# ADC.net
KiCad netlist of a schematic drawn in Altium Designer
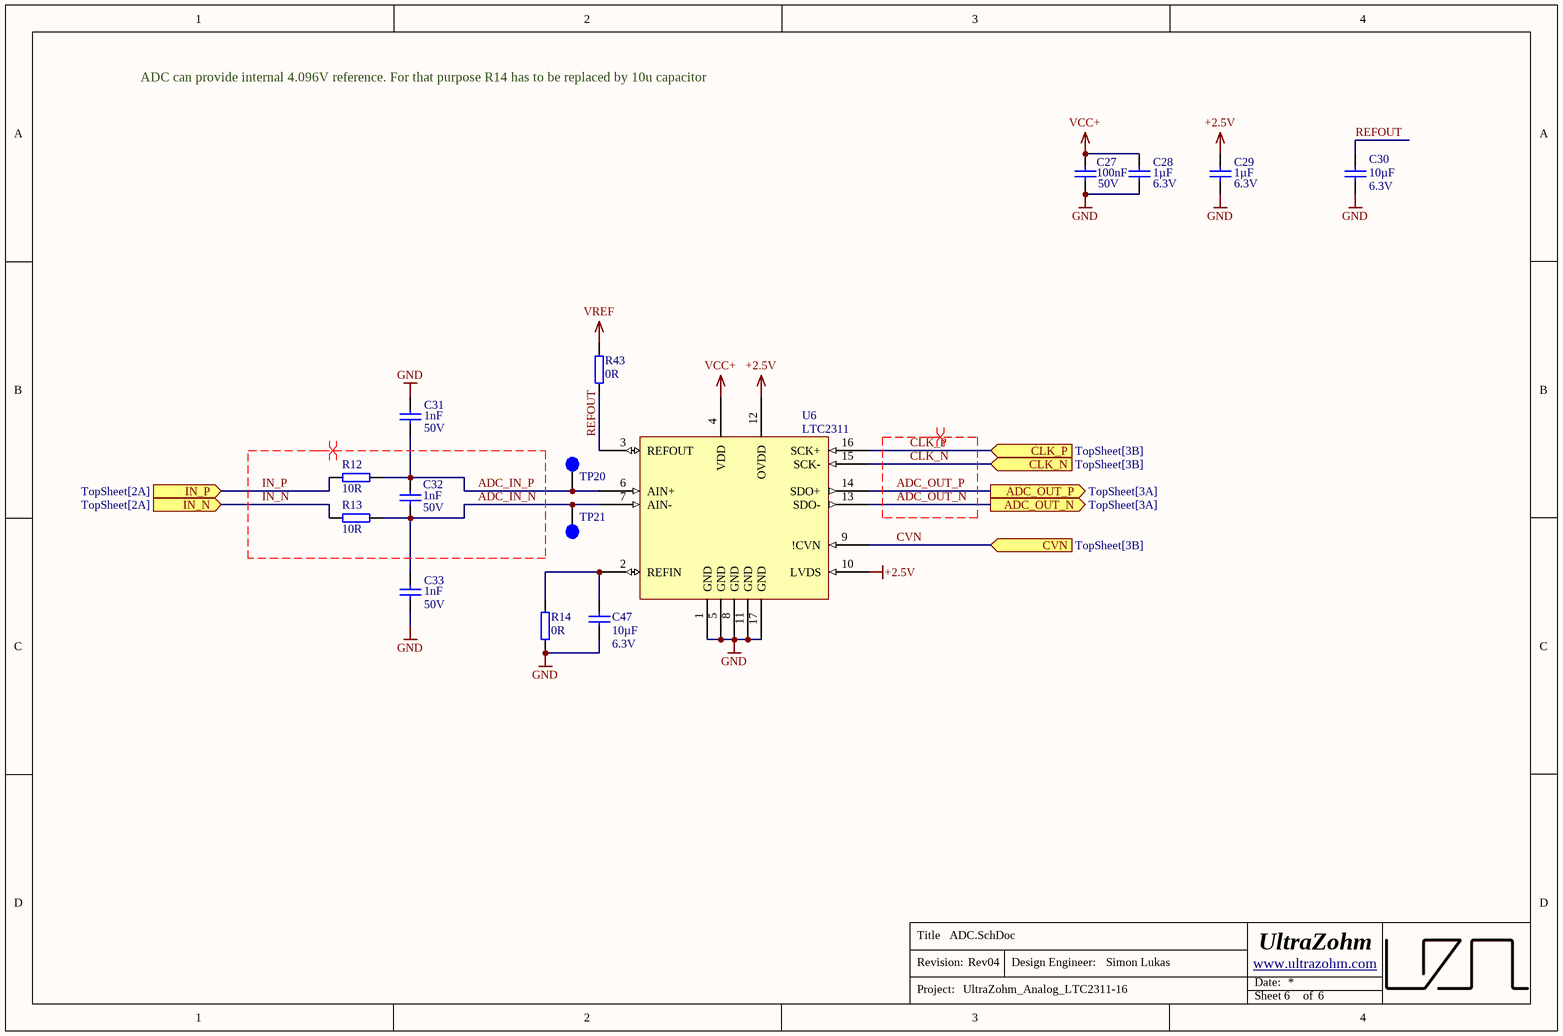
[diagram p0: ADC.SchDoc]

(export (version "E")
  (design (tool "Eeschema 10.0.6"))
  (components
    (comp (ref "C27")
      (value "100nF")
      (footprint "CAPC1608X07N")
      (fields
        (field (name "MF") "Yageo")
        (field (name "MPN") "CC0603KRX7R9BB104")
        (field (name "VOLTAGE") "50V")
      )
      (libsource (lib "UltraZohm_ADC") (part "Cap_0603"))
    )
    (comp (ref "C28")
      (value "1µF")
      (footprint "CAPC1608X07N")
      (fields
        (field (name "MF") "Taiyo Yuden")
        (field (name "MPN") "JMK107BJ105MA-T")
        (field (name "VOLTAGE") "6.3V")
      )
      (libsource (lib "UltraZohm_ADC") (part "Cap_0603"))
    )
    (comp (ref "C29")
      (value "1µF")
      (footprint "CAPC1608X07N")
      (fields
        (field (name "MF") "Taiyo Yuden")
        (field (name "MPN") "JMK107BJ105MA-T")
        (field (name "VOLTAGE") "6.3V")
      )
      (libsource (lib "UltraZohm_ADC") (part "Cap_0603"))
    )
    (comp (ref "C30")
      (value "10µF")
      (footprint "Cap0805")
      (description "CAP CER 0805")
      (fields
        (field (name "MF") "Samsung Electro-Mechanics")
        (field (name "MPN") "CL21A106KQFNNNE")
        (field (name "VOLTAGE") "6.3V")
      )
      (libsource (lib "UltraZohm_ADC") (part "Cap0805"))
    )
    (comp (ref "C31")
      (value "1nF")
      (footprint "CAPC1608X07N")
      (fields
        (field (name "MF") "Murata")
        (field (name "MPN") "GRM1885C1H102GA1D")
        (field (name "VOLTAGE") "50V")
      )
      (libsource (lib "UltraZohm_ADC") (part "Cap_0603"))
    )
    (comp (ref "C32")
      (value "1nF")
      (footprint "CAPC1608X07N")
      (fields
        (field (name "MF") "Murata")
        (field (name "MPN") "GRM1885C1H102GA1D")
        (field (name "VOLTAGE") "50V")
      )
      (libsource (lib "UltraZohm_ADC") (part "Cap_0603"))
    )
    (comp (ref "C33")
      (value "1nF")
      (footprint "CAPC1608X07N")
      (fields
        (field (name "MF") "Murata")
        (field (name "MPN") "GRM1885C1H102GA1D")
        (field (name "VOLTAGE") "50V")
      )
      (libsource (lib "UltraZohm_ADC") (part "Cap_0603"))
    )
    (comp (ref "C47")
      (value "10µF")
      (footprint "Cap0805")
      (description "CAP CER 0805")
      (fields
        (field (name "MF") "Samsung Electro-Mechanics")
        (field (name "MPN") "CL21A106KQFNNNE")
        (field (name "VOLTAGE") "6.3V")
      )
      (libsource (lib "UltraZohm_ADC") (part "Cap0805"))
    )
    (comp (ref "R12")
      (value "10R")
      (footprint "RESC1608X06N")
      (fields (field (name "MF") "Yageo") (field (name "MPN") "RC0603FR-0710RL"))
      (libsource (lib "UltraZohm_ADC") (part "R_0603"))
    )
    (comp (ref "R13")
      (value "10R")
      (footprint "RESC1608X06N")
      (fields (field (name "MF") "Yageo") (field (name "MPN") "RC0603FR-0710RL"))
      (libsource (lib "UltraZohm_ADC") (part "R_0603"))
    )
    (comp (ref "R14")
      (value "0R")
      (footprint "RESC1608X06N")
      (fields (field (name "MF") "Vishay / Dale") (field (name "MPN") "CRCW06030000Z0EBC"))
      (libsource (lib "UltraZohm_ADC") (part "R_0603"))
    )
    (comp (ref "R43")
      (value "0R")
      (footprint "RESC1608X06N")
      (fields (field (name "MF") "Vishay / Dale") (field (name "MPN") "CRCW06030000Z0EBC"))
      (libsource (lib "UltraZohm_ADC") (part "R_0603"))
    )
    (comp (ref "TP20")
      (value "+")
      (footprint "TP_1mm")
      (description "Testpoint 1mm")
      (fields (field (name "CREATED") "2018_06_25_AGeiger"))
      (libsource (lib "UltraZohm_ADC") (part "TP_1mm"))
    )
    (comp (ref "TP21")
      (value "-")
      (footprint "TP_1mm")
      (description "Testpoint 1mm")
      (fields (field (name "CREATED") "2018_06_25_AGeiger"))
      (libsource (lib "UltraZohm_ADC") (part "TP_1mm"))
    )
    (comp (ref "U6")
      (value "LTC2311")
      (footprint "TSSOP50P510X110_HS-17N")
      (description "16 Bit SAR ADC, 5MSps")
      (fields (field (name "MF") "Analog Devices") (field (name "MPN") "LTC2311CMSE-16#PBF"))
      (libsource (lib "UltraZohm_ADC") (part "LTC2311-16"))
    )
  )
  (nets
    (net (code "1") (name "+2.5V") (class "Default")
      (node (ref "C29") (pin "1") (pinfunction "1_1") (pintype "passive"))
      (node (ref "U6") (pin "10") (pinfunction "LVDS_10") (pintype "input"))
      (node (ref "U6") (pin "12") (pinfunction "OVDD_12") (pintype "power_in"))
    )
    (net (code "2") (name "/ADC_IN_N") (class "Default")
      (node (ref "C32") (pin "2") (pinfunction "2_2") (pintype "passive"))
      (node (ref "C33") (pin "1") (pinfunction "1_1") (pintype "passive"))
      (node (ref "R13") (pin "2") (pintype "passive"))
      (node (ref "TP21") (pin "1") (pintype "passive"))
      (node (ref "U6") (pin "7") (pinfunction "AIN-_7") (pintype "input"))
    )
    (net (code "3") (name "/ADC_IN_P") (class "Default")
      (node (ref "C31") (pin "2") (pinfunction "2_2") (pintype "passive"))
      (node (ref "C32") (pin "1") (pinfunction "1_1") (pintype "passive"))
      (node (ref "R12") (pin "2") (pintype "passive"))
      (node (ref "TP20") (pin "1") (pintype "passive"))
      (node (ref "U6") (pin "6") (pinfunction "AIN+_6") (pintype "input"))
    )
    (net (code "4") (name "/ADC_OUT_N") (class "Default")
      (node (ref "U6") (pin "13") (pinfunction "SDO-_13") (pintype "output"))
    )
    (net (code "5") (name "/ADC_OUT_P") (class "Default")
      (node (ref "U6") (pin "14") (pinfunction "SDO+_14") (pintype "output"))
    )
    (net (code "6") (name "/CLK_N") (class "Default")
      (node (ref "U6") (pin "15") (pinfunction "SCK-_15") (pintype "input"))
    )
    (net (code "7") (name "/CLK_P") (class "Default")
      (node (ref "U6") (pin "16") (pinfunction "SCK+_16") (pintype "input"))
    )
    (net (code "8") (name "/CVN") (class "Default")
      (node (ref "U6") (pin "9") (pinfunction "!CVN_9") (pintype "input"))
    )
    (net (code "9") (name "/IN_N") (class "Default") (node (ref "R13") (pin "1") (pintype "passive")))
    (net (code "10") (name "/IN_P") (class "Default") (node (ref "R12") (pin "1") (pintype "passive")))
    (net (code "11") (name "/REFOUT") (class "Default")
      (node (ref "C30") (pin "1") (pinfunction "1_1") (pintype "passive"))
      (node (ref "R43") (pin "1") (pintype "passive"))
      (node (ref "U6") (pin "3") (pinfunction "REFOUT_3") (pintype "bidirectional"))
    )
    (net (code "12") (name "GND") (class "Default")
      (node (ref "C27") (pin "2") (pinfunction "2_2") (pintype "passive"))
      (node (ref "C28") (pin "2") (pinfunction "2_2") (pintype "passive"))
      (node (ref "C29") (pin "2") (pinfunction "2_2") (pintype "passive"))
      (node (ref "C30") (pin "2") (pinfunction "2_2") (pintype "passive"))
      (node (ref "C31") (pin "1") (pinfunction "1_1") (pintype "passive"))
      (node (ref "C33") (pin "2") (pinfunction "2_2") (pintype "passive"))
      (node (ref "C47") (pin "2") (pinfunction "2_2") (pintype "passive"))
      (node (ref "R14") (pin "1") (pintype "passive"))
      (node (ref "U6") (pin "1") (pinfunction "GND_1") (pintype "power_in"))
      (node (ref "U6") (pin "11") (pinfunction "GND_11") (pintype "power_in"))
      (node (ref "U6") (pin "17") (pinfunction "GND_17") (pintype "power_in"))
      (node (ref "U6") (pin "5") (pinfunction "GND_5") (pintype "power_in"))
      (node (ref "U6") (pin "8") (pinfunction "GND_8") (pintype "power_in"))
    )
    (net (code "13") (name "Net-(U6-REFIN)") (class "Default")
      (node (ref "C47") (pin "1") (pinfunction "1_1") (pintype "passive"))
      (node (ref "R14") (pin "2") (pintype "passive"))
      (node (ref "U6") (pin "2") (pinfunction "REFIN_2") (pintype "bidirectional"))
    )
    (net (code "14") (name "VCC+") (class "Default")
      (node (ref "C27") (pin "1") (pinfunction "1_1") (pintype "passive"))
      (node (ref "C28") (pin "1") (pinfunction "1_1") (pintype "passive"))
      (node (ref "U6") (pin "4") (pinfunction "VDD_4") (pintype "power_in"))
    )
    (net (code "15") (name "VREF") (class "Default") (node (ref "R43") (pin "2") (pintype "passive")))
  )
)
